# epic.net
KiCad netlist of a schematic drawn in Altium Designer
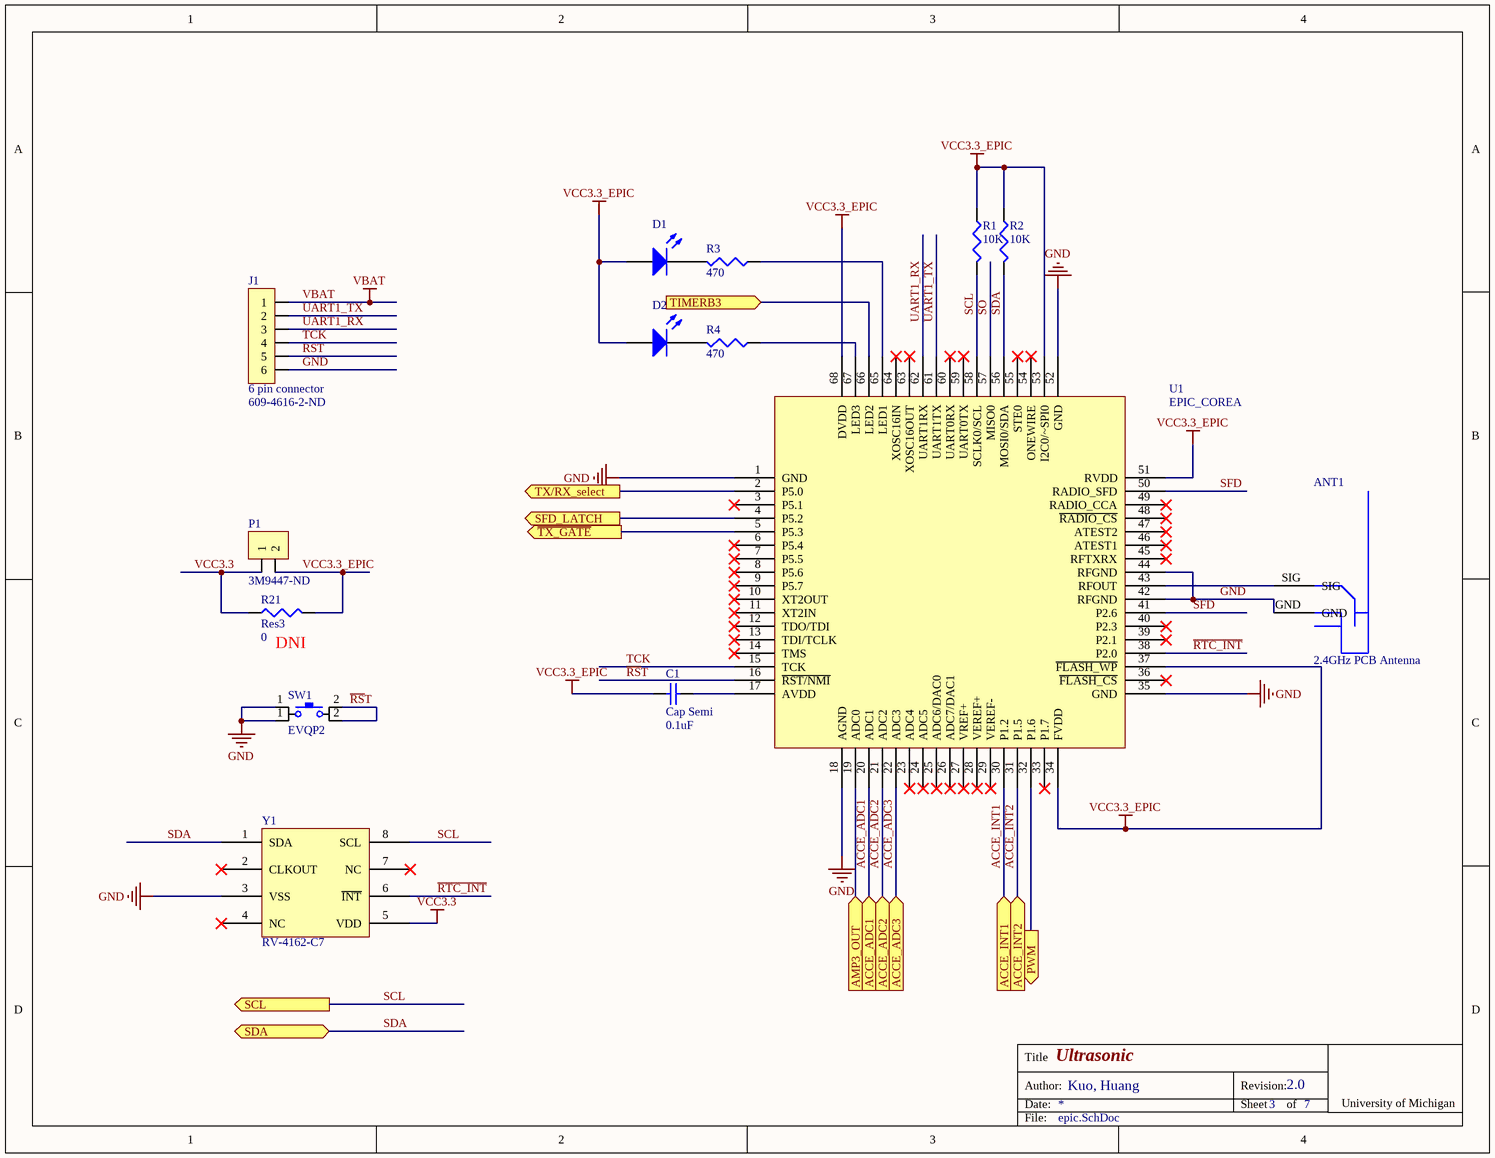
[diagram p0: epic.SchDoc]

(export (version "E")
  (design (tool "Eeschema 10.0.6"))
  (components
    (comp (ref "ANT1")
      (value "2.4GHz PCB Antenna")
      (footprint "Inverted F Antenna")
      (libsource (lib "ultrasounic") (part "2.4GHz PCB Antenna"))
    )
    (comp (ref "C1")
      (value "Cap Semi")
      (footprint "1608[0603]")
      (description "Capacitor (Semiconductor SIM Model)")
      (fields (field (name "ALTIUM_VALUE") "0.1uF") (field (name "PUBLISHER") "Altium Limited"))
      (libsource (lib "Miscellaneous Devices") (part "Cap Semi"))
    )
    (comp (ref "D1")
      (value "LED3")
      (footprint "J1-0603")
      (description "Typical BLUE SiC LED")
      (fields (field (name "PUBLISHER") "Altium Limited"))
      (libsource (lib "Miscellaneous Devices") (part "LED3"))
    )
    (comp (ref "D2")
      (value "LED3")
      (footprint "J1-0603")
      (description "Typical BLUE SiC LED")
      (fields (field (name "PUBLISHER") "Altium Limited"))
      (libsource (lib "Miscellaneous Devices") (part "LED3"))
    )
    (comp (ref "J1")
      (value "6 pin connector")
      (footprint "Micro USB")
      (fields (field (name "SUPPLIER PART NUMBER 2") "609-4616-2-ND"))
      (libsource (lib "ultrasounic") (part "6 pin connector"))
    )
    (comp (ref "P1")
      (value "1 x 2 header")
      (footprint "1x2 header")
      (description "100 mils standard header")
      (fields (field (name "SUPPLIER PART NUMBER 1") "3M9447-ND"))
      (libsource (lib "ultrasounic") (part "1 x 2 header"))
    )
    (comp (ref "R1")
      (value "10K")
      (footprint "J1-0603")
      (description "Resistor")
      (fields (field (name "PUBLISHER") "Altium Limited"))
      (libsource (lib "Miscellaneous Devices") (part "Res3"))
    )
    (comp (ref "R2")
      (value "10K")
      (footprint "J1-0603")
      (description "Resistor")
      (fields (field (name "PUBLISHER") "Altium Limited"))
      (libsource (lib "Miscellaneous Devices") (part "Res3"))
    )
    (comp (ref "R3")
      (value "470")
      (footprint "J1-0603")
      (description "Resistor")
      (fields (field (name "PUBLISHER") "Altium Limited"))
      (libsource (lib "Miscellaneous Devices") (part "Res3"))
    )
    (comp (ref "R4")
      (value "470")
      (footprint "J1-0603")
      (description "Resistor")
      (fields (field (name "PUBLISHER") "Altium Limited"))
      (libsource (lib "Miscellaneous Devices") (part "Res3"))
    )
    (comp (ref "R21")
      (value "Res3")
      (footprint "J1-0603")
      (description "Resistor")
      (fields (field (name "ALTIUM_VALUE") "0") (field (name "PUBLISHER") "Altium Limited"))
      (libsource (lib "Miscellaneous Devices") (part "Res3"))
    )
    (comp (ref "SW1")
      (value "EVQP2")
      (footprint "EVQP2")
      (description "Switch")
      (libsource (lib "ultrasounic") (part "EVQP2"))
    )
    (comp (ref "U1")
      (value "EPIC_COREA")
      (footprint "EPIC_LCC68")
      (description "EPIC Core")
      (libsource (lib "ultrasounic") (part "EPIC_COREA"))
    )
    (comp (ref "Y1")
      (value "RV-4162-C7")
      (footprint "RV4162")
      (description "Real Time Clock Module with I2C Bus")
      (libsource (lib "ultrasounic") (part "RV-4162-C7"))
    )
  )
  (nets
    (net (code "1") (name "/ACCE_ADC1") (class "Default")
      (node (ref "U1") (pin "20") (pinfunction "ADC1_20") (pintype "passive"))
    )
    (net (code "2") (name "/ACCE_ADC2") (class "Default")
      (node (ref "U1") (pin "21") (pinfunction "ADC2_21") (pintype "passive"))
    )
    (net (code "3") (name "/ACCE_ADC3") (class "Default")
      (node (ref "U1") (pin "22") (pinfunction "ADC3_22") (pintype "passive"))
    )
    (net (code "4") (name "/ACCE_INT1") (class "Default")
      (node (ref "U1") (pin "30") (pinfunction "P1.2_30") (pintype "passive"))
    )
    (net (code "5") (name "/ACCE_INT2") (class "Default")
      (node (ref "U1") (pin "31") (pinfunction "P1.5_31") (pintype "passive"))
    )
    (net (code "6") (name "/AMP3_OUT") (class "Default")
      (node (ref "U1") (pin "19") (pinfunction "ADC0_19") (pintype "passive"))
    )
    (net (code "7") (name "/PWM") (class "Default")
      (node (ref "U1") (pin "32") (pinfunction "P1.6_32") (pintype "passive"))
    )
    (net (code "8") (name "/SCL") (class "Default")
      (node (ref "R1") (pin "2") (pinfunction "2_2") (pintype "passive"))
      (node (ref "U1") (pin "58") (pinfunction "SCLK0/SCL_58") (pintype "passive"))
      (node (ref "Y1") (pin "8") (pinfunction "SCL_8") (pintype "passive"))
    )
    (net (code "9") (name "/SDA") (class "Default")
      (node (ref "R2") (pin "2") (pinfunction "2_2") (pintype "passive"))
      (node (ref "U1") (pin "56") (pinfunction "MOSI0/SDA_56") (pintype "passive"))
      (node (ref "Y1") (pin "1") (pinfunction "SDA_1") (pintype "passive"))
    )
    (net (code "10") (name "/SFD") (class "Default")
      (node (ref "U1") (pin "41") (pinfunction "P2.6_41") (pintype "passive"))
      (node (ref "U1") (pin "50") (pinfunction "RADIO_SFD_50") (pintype "passive"))
    )
    (net (code "11") (name "/SFD_LATCH") (class "Default")
      (node (ref "U1") (pin "4") (pinfunction "P5.2_4") (pintype "passive"))
    )
    (net (code "12") (name "/SO") (class "Default")
      (node (ref "U1") (pin "57") (pinfunction "MISO0_57") (pintype "passive"))
    )
    (net (code "13") (name "/TCK") (class "Default")
      (node (ref "J1") (pin "4") (pinfunction "4_4") (pintype "passive"))
      (node (ref "U1") (pin "15") (pinfunction "TCK_15") (pintype "passive"))
    )
    (net (code "14") (name "/TIMERB3") (class "Default")
      (node (ref "U1") (pin "66") (pinfunction "LED2_66") (pintype "passive"))
    )
    (net (code "15") (name "/TX{slash}RX_select") (class "Default")
      (node (ref "U1") (pin "2") (pinfunction "P5.0_2") (pintype "passive"))
    )
    (net (code "16") (name "/UART1_RX") (class "Default")
      (node (ref "J1") (pin "3") (pinfunction "3_3") (pintype "passive"))
      (node (ref "U1") (pin "62") (pinfunction "UART1RX_62") (pintype "passive"))
    )
    (net (code "17") (name "/UART1_TX") (class "Default")
      (node (ref "J1") (pin "2") (pinfunction "2_2") (pintype "passive"))
      (node (ref "U1") (pin "61") (pinfunction "UART1TX_61") (pintype "passive"))
    )
    (net (code "18") (name "/~{RS}T") (class "Default")
      (node (ref "J1") (pin "5") (pinfunction "5_5") (pintype "passive"))
      (node (ref "SW1") (pin "2") (pinfunction "2_2") (pintype "passive"))
      (node (ref "U1") (pin "16") (pinfunction "~{RST/NMI}_16") (pintype "passive"))
    )
    (net (code "19") (name "/~{RTC_INT}") (class "Default")
      (node (ref "U1") (pin "38") (pinfunction "P2.0_38") (pintype "passive"))
      (node (ref "Y1") (pin "6") (pinfunction "~{INT}_6") (pintype "passive"))
    )
    (net (code "20") (name "/~{TX_GATE}") (class "Default")
      (node (ref "U1") (pin "5") (pinfunction "P5.3_5") (pintype "passive"))
    )
    (net (code "21") (name "GND") (class "Default")
      (node (ref "ANT1") (pin "GND") (pinfunction "GND_GND") (pintype "passive"))
      (node (ref "J1") (pin "6") (pinfunction "6_6") (pintype "passive"))
      (node (ref "SW1") (pin "1") (pinfunction "1_1") (pintype "passive"))
      (node (ref "U1") (pin "1") (pinfunction "GND_1") (pintype "passive"))
      (node (ref "U1") (pin "18") (pinfunction "AGND_18") (pintype "passive"))
      (node (ref "U1") (pin "35") (pinfunction "GND_35") (pintype "passive"))
      (node (ref "U1") (pin "42") (pinfunction "RFGND_42") (pintype "passive"))
      (node (ref "U1") (pin "44") (pinfunction "RFGND_44") (pintype "passive"))
      (node (ref "U1") (pin "52") (pinfunction "GND_52") (pintype "passive"))
      (node (ref "Y1") (pin "3") (pinfunction "VSS_3") (pintype "passive"))
    )
    (net (code "22") (name "Net-(D1-K)") (class "Default")
      (node (ref "D1") (pin "2") (pinfunction "K_2") (pintype "passive"))
      (node (ref "R3") (pin "2") (pinfunction "2_2") (pintype "passive"))
    )
    (net (code "23") (name "Net-(D2-K)") (class "Default")
      (node (ref "D2") (pin "2") (pinfunction "K_2") (pintype "passive"))
      (node (ref "R4") (pin "2") (pinfunction "2_2") (pintype "passive"))
    )
    (net (code "24") (name "Net-(U1-AVDD)") (class "Default")
      (node (ref "C1") (pin "2") (pinfunction "2_2") (pintype "passive"))
      (node (ref "U1") (pin "17") (pinfunction "AVDD_17") (pintype "passive"))
    )
    (net (code "25") (name "Net-(U1-LED1)") (class "Default")
      (node (ref "R3") (pin "1") (pinfunction "1_1") (pintype "passive"))
      (node (ref "U1") (pin "65") (pinfunction "LED1_65") (pintype "passive"))
    )
    (net (code "26") (name "Net-(U1-LED3)") (class "Default")
      (node (ref "R4") (pin "1") (pinfunction "1_1") (pintype "passive"))
      (node (ref "U1") (pin "67") (pinfunction "LED3_67") (pintype "passive"))
    )
    (net (code "27") (name "Net-(U1-RFOUT)") (class "Default")
      (node (ref "ANT1") (pin "SIG") (pinfunction "SIG_SIG") (pintype "passive"))
      (node (ref "U1") (pin "43") (pinfunction "RFOUT_43") (pintype "passive"))
    )
    (net (code "28") (name "VBAT") (class "Default")
      (node (ref "J1") (pin "1") (pinfunction "1_1") (pintype "passive"))
    )
    (net (code "29") (name "VCC3.3") (class "Default")
      (node (ref "P1") (pin "1") (pinfunction "1_1") (pintype "passive"))
      (node (ref "R21") (pin "1") (pinfunction "1_1") (pintype "passive"))
      (node (ref "Y1") (pin "5") (pinfunction "VDD_5") (pintype "passive"))
    )
    (net (code "30") (name "VCC3.3_EPIC") (class "Default")
      (node (ref "C1") (pin "1") (pinfunction "1_1") (pintype "passive"))
      (node (ref "D1") (pin "1") (pinfunction "A_1") (pintype "passive"))
      (node (ref "D2") (pin "1") (pinfunction "A_1") (pintype "passive"))
      (node (ref "P1") (pin "2") (pinfunction "2_2") (pintype "passive"))
      (node (ref "R1") (pin "1") (pinfunction "1_1") (pintype "passive"))
      (node (ref "R2") (pin "1") (pinfunction "1_1") (pintype "passive"))
      (node (ref "R21") (pin "2") (pinfunction "2_2") (pintype "passive"))
      (node (ref "U1") (pin "34") (pinfunction "FVDD_34") (pintype "passive"))
      (node (ref "U1") (pin "37") (pinfunction "~{FLASH_WP}_37") (pintype "passive"))
      (node (ref "U1") (pin "51") (pinfunction "RVDD_51") (pintype "passive"))
      (node (ref "U1") (pin "53") (pinfunction "I2C0/~SPI0_53") (pintype "passive"))
      (node (ref "U1") (pin "68") (pinfunction "DVDD_68") (pintype "passive"))
    )
    (net (code "31") (name "unconnected-(U1-ADC4-Pad23)") (class "Default")
      (node (ref "U1") (pin "23") (pinfunction "ADC4_23") (pintype "passive+no_connect"))
    )
    (net (code "32") (name "unconnected-(U1-ADC5-Pad24)") (class "Default")
      (node (ref "U1") (pin "24") (pinfunction "ADC5_24") (pintype "passive+no_connect"))
    )
    (net (code "33") (name "unconnected-(U1-ADC6{slash}DAC0-Pad25)") (class "Default")
      (node (ref "U1") (pin "25") (pinfunction "ADC6/DAC0_25") (pintype "passive+no_connect"))
    )
    (net (code "34") (name "unconnected-(U1-ADC7{slash}DAC1-Pad26)") (class "Default")
      (node (ref "U1") (pin "26") (pinfunction "ADC7/DAC1_26") (pintype "passive+no_connect"))
    )
    (net (code "35") (name "unconnected-(U1-ATEST1-Pad46)") (class "Default")
      (node (ref "U1") (pin "46") (pinfunction "ATEST1_46") (pintype "passive+no_connect"))
    )
    (net (code "36") (name "unconnected-(U1-ATEST2-Pad47)") (class "Default")
      (node (ref "U1") (pin "47") (pinfunction "ATEST2_47") (pintype "passive+no_connect"))
    )
    (net (code "37") (name "unconnected-(U1-ONEWIRE-Pad54)") (class "Default")
      (node (ref "U1") (pin "54") (pinfunction "ONEWIRE_54") (pintype "passive+no_connect"))
    )
    (net (code "38") (name "unconnected-(U1-P1.7-Pad33)") (class "Default")
      (node (ref "U1") (pin "33") (pinfunction "P1.7_33") (pintype "passive+no_connect"))
    )
    (net (code "39") (name "unconnected-(U1-P2.1-Pad39)") (class "Default")
      (node (ref "U1") (pin "39") (pinfunction "P2.1_39") (pintype "passive+no_connect"))
    )
    (net (code "40") (name "unconnected-(U1-P2.3-Pad40)") (class "Default")
      (node (ref "U1") (pin "40") (pinfunction "P2.3_40") (pintype "passive+no_connect"))
    )
    (net (code "41") (name "unconnected-(U1-P5.1-Pad3)") (class "Default")
      (node (ref "U1") (pin "3") (pinfunction "P5.1_3") (pintype "passive+no_connect"))
    )
    (net (code "42") (name "unconnected-(U1-P5.4-Pad6)") (class "Default")
      (node (ref "U1") (pin "6") (pinfunction "P5.4_6") (pintype "passive+no_connect"))
    )
    (net (code "43") (name "unconnected-(U1-P5.5-Pad7)") (class "Default")
      (node (ref "U1") (pin "7") (pinfunction "P5.5_7") (pintype "passive+no_connect"))
    )
    (net (code "44") (name "unconnected-(U1-P5.6-Pad8)") (class "Default")
      (node (ref "U1") (pin "8") (pinfunction "P5.6_8") (pintype "passive+no_connect"))
    )
    (net (code "45") (name "unconnected-(U1-P5.7-Pad9)") (class "Default")
      (node (ref "U1") (pin "9") (pinfunction "P5.7_9") (pintype "passive+no_connect"))
    )
    (net (code "46") (name "unconnected-(U1-RADIO_CCA-Pad49)") (class "Default")
      (node (ref "U1") (pin "49") (pinfunction "RADIO_CCA_49") (pintype "passive+no_connect"))
    )
    (net (code "47") (name "unconnected-(U1-RFTXRX-Pad45)") (class "Default")
      (node (ref "U1") (pin "45") (pinfunction "RFTXRX_45") (pintype "passive+no_connect"))
    )
    (net (code "48") (name "unconnected-(U1-STE0-Pad55)") (class "Default")
      (node (ref "U1") (pin "55") (pinfunction "STE0_55") (pintype "passive+no_connect"))
    )
    (net (code "49") (name "unconnected-(U1-TDI{slash}TCLK-Pad13)") (class "Default")
      (node (ref "U1") (pin "13") (pinfunction "TDI/TCLK_13") (pintype "passive+no_connect"))
    )
    (net (code "50") (name "unconnected-(U1-TDO{slash}TDI-Pad12)") (class "Default")
      (node (ref "U1") (pin "12") (pinfunction "TDO/TDI_12") (pintype "passive+no_connect"))
    )
    (net (code "51") (name "unconnected-(U1-TMS-Pad14)") (class "Default")
      (node (ref "U1") (pin "14") (pinfunction "TMS_14") (pintype "passive+no_connect"))
    )
    (net (code "52") (name "unconnected-(U1-UART0RX-Pad60)") (class "Default")
      (node (ref "U1") (pin "60") (pinfunction "UART0RX_60") (pintype "passive+no_connect"))
    )
    (net (code "53") (name "unconnected-(U1-UART0TX-Pad59)") (class "Default")
      (node (ref "U1") (pin "59") (pinfunction "UART0TX_59") (pintype "passive+no_connect"))
    )
    (net (code "54") (name "unconnected-(U1-VEREF+-Pad28)") (class "Default")
      (node (ref "U1") (pin "28") (pinfunction "VEREF+_28") (pintype "passive+no_connect"))
    )
    (net (code "55") (name "unconnected-(U1-VEREF--Pad29)") (class "Default")
      (node (ref "U1") (pin "29") (pinfunction "VEREF-_29") (pintype "passive+no_connect"))
    )
    (net (code "56") (name "unconnected-(U1-VREF+-Pad27)") (class "Default")
      (node (ref "U1") (pin "27") (pinfunction "VREF+_27") (pintype "passive+no_connect"))
    )
    (net (code "57") (name "unconnected-(U1-XOSC16IN-Pad64)") (class "Default")
      (node (ref "U1") (pin "64") (pinfunction "XOSC16IN_64") (pintype "passive+no_connect"))
    )
    (net (code "58") (name "unconnected-(U1-XOSC16OUT-Pad63)") (class "Default")
      (node (ref "U1") (pin "63") (pinfunction "XOSC16OUT_63") (pintype "passive+no_connect"))
    )
    (net (code "59") (name "unconnected-(U1-XT2IN-Pad11)") (class "Default")
      (node (ref "U1") (pin "11") (pinfunction "XT2IN_11") (pintype "passive+no_connect"))
    )
    (net (code "60") (name "unconnected-(U1-XT2OUT-Pad10)") (class "Default")
      (node (ref "U1") (pin "10") (pinfunction "XT2OUT_10") (pintype "passive+no_connect"))
    )
    (net (code "61") (name "unconnected-(U1-~{FLASH_CS}-Pad36)") (class "Default")
      (node (ref "U1") (pin "36") (pinfunction "~{FLASH_CS}_36") (pintype "passive+no_connect"))
    )
    (net (code "62") (name "unconnected-(U1-~{RADIO_CS}-Pad48)") (class "Default")
      (node (ref "U1") (pin "48") (pinfunction "~{RADIO_CS}_48") (pintype "passive+no_connect"))
    )
    (net (code "63") (name "unconnected-(Y1-CLKOUT-Pad2)") (class "Default")
      (node (ref "Y1") (pin "2") (pinfunction "CLKOUT_2") (pintype "passive+no_connect"))
    )
    (net (code "64") (name "unconnected-(Y1-NC-Pad4)") (class "Default")
      (node (ref "Y1") (pin "4") (pinfunction "NC_4") (pintype "passive+no_connect"))
    )
    (net (code "65") (name "unconnected-(Y1-NC-Pad7)") (class "Default")
      (node (ref "Y1") (pin "7") (pinfunction "NC_7") (pintype "passive+no_connect"))
    )
  )
)
